# design.net
KiCad netlist of a schematic drawn in Altium Designer
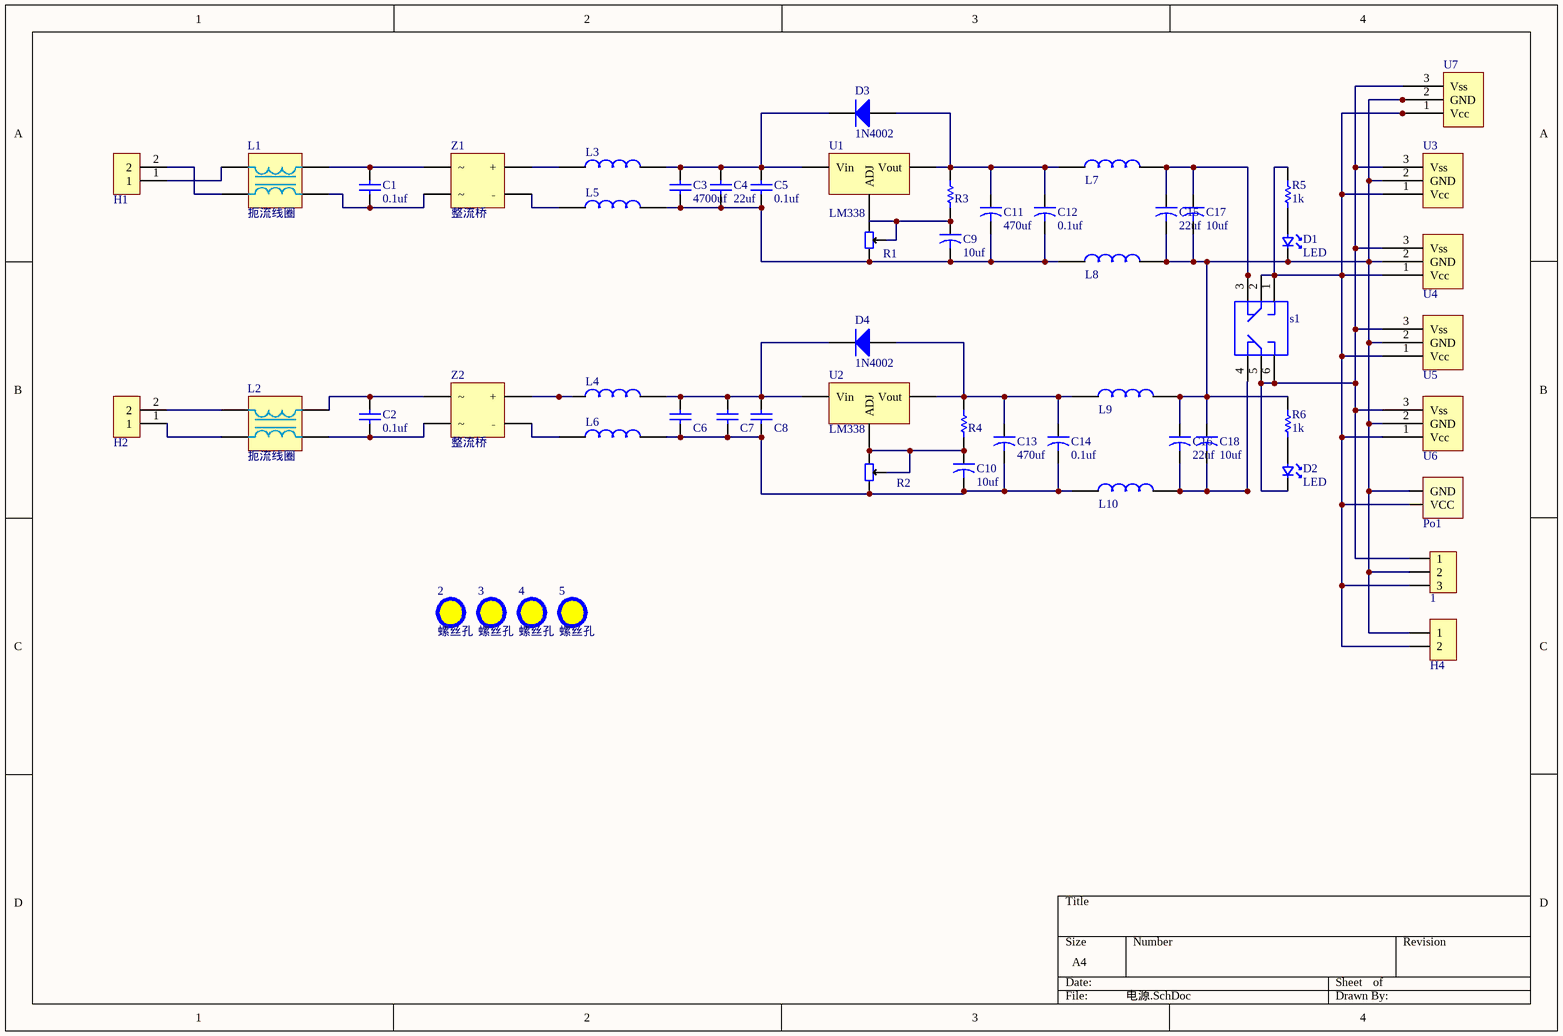
[diagram p0: 电源.SchDoc]

(export (version "E")
  (design (tool "Eeschema 10.0.6"))
  (components
    (comp (ref "1")
      (value "KF128-5.08-3P")
      (footprint "KF128-5.08-3P")
      (libsource (lib "Mylib_Connectors") (part "KF128-5.08-3P"))
    )
    (comp (ref "2") (value "螺丝孔") (footprint "固定过孔") (libsource (lib "Mylib_Connectors") (part "螺丝孔")))
    (comp (ref "3") (value "螺丝孔") (footprint "固定过孔") (libsource (lib "Mylib_Connectors") (part "螺丝孔")))
    (comp (ref "4") (value "螺丝孔") (footprint "固定过孔") (libsource (lib "Mylib_Connectors") (part "螺丝孔")))
    (comp (ref "5") (value "螺丝孔") (footprint "固定过孔") (libsource (lib "Mylib_Connectors") (part "螺丝孔")))
    (comp (ref "C1")
      (value "~")
      (footprint "安规电容")
      (fields (field (name "值") "0.1uf"))
      (libsource (lib "SCH_lib_tao") (part "Cap1"))
    )
    (comp (ref "C2")
      (value "Cap1")
      (footprint "安规电容")
      (fields (field (name "值") "0.1uf"))
      (libsource (lib "SCH_lib_tao") (part "Cap1"))
    )
    (comp (ref "C3")
      (value "Cap1")
      (footprint "4700UF_50V")
      (fields (field (name "值") "4700uf"))
      (libsource (lib "SCH_lib_tao") (part "Cap1"))
    )
    (comp (ref "C4")
      (value "Cap1")
      (footprint "22UF_50V")
      (fields (field (name "值") "22uf"))
      (libsource (lib "SCH_lib_tao") (part "Cap1"))
    )
    (comp (ref "C5")
      (value "Cap1")
      (footprint "独石电容")
      (fields (field (name "值") "0.1uf"))
      (libsource (lib "SCH_lib_tao") (part "Cap1"))
    )
    (comp (ref "C6") (value "Cap1") (footprint "4700UF_50V") (libsource (lib "SCH_lib_tao") (part "Cap1")))
    (comp (ref "C7") (value "Cap1") (footprint "22UF_50V") (libsource (lib "SCH_lib_tao") (part "Cap1")))
    (comp (ref "C8") (value "Cap1") (footprint "独石电容") (libsource (lib "SCH_lib_tao") (part "Cap1")))
    (comp (ref "C9")
      (value "Cap")
      (footprint "陶瓷电容")
      (fields (field (name "值") "10uf"))
      (libsource (lib "SCH_lib_tao") (part "Cap"))
    )
    (comp (ref "C10")
      (value "Cap")
      (footprint "陶瓷电容")
      (fields (field (name "值") "10uf"))
      (libsource (lib "SCH_lib_tao") (part "Cap"))
    )
    (comp (ref "C11")
      (value "Cap")
      (footprint "C DIP DIA6.3")
      (fields (field (name "值") "470uf"))
      (libsource (lib "SCH_lib_tao") (part "Cap"))
    )
    (comp (ref "C12")
      (value "Cap")
      (footprint "陶瓷电容")
      (fields (field (name "值") "0.1uf"))
      (libsource (lib "SCH_lib_tao") (part "Cap"))
    )
    (comp (ref "C13")
      (value "Cap")
      (footprint "C DIP DIA6.3")
      (fields (field (name "值") "470uf"))
      (libsource (lib "SCH_lib_tao") (part "Cap"))
    )
    (comp (ref "C14")
      (value "Cap")
      (footprint "陶瓷电容")
      (fields (field (name "值") "0.1uf"))
      (libsource (lib "SCH_lib_tao") (part "Cap"))
    )
    (comp (ref "C15")
      (value "Cap")
      (footprint "22UF_50V")
      (fields (field (name "值") "22uf"))
      (libsource (lib "SCH_lib_tao") (part "Cap"))
    )
    (comp (ref "C16")
      (value "Cap")
      (footprint "22UF_50V")
      (fields (field (name "值") "22uf"))
      (libsource (lib "SCH_lib_tao") (part "Cap"))
    )
    (comp (ref "C17")
      (value "Cap")
      (footprint "陶瓷电容")
      (fields (field (name "值") "10uf"))
      (libsource (lib "SCH_lib_tao") (part "Cap"))
    )
    (comp (ref "C18")
      (value "Cap")
      (footprint "陶瓷电容")
      (fields (field (name "值") "10uf"))
      (libsource (lib "SCH_lib_tao") (part "Cap"))
    )
    (comp (ref "D1") (value "LED") (footprint "0805_s") (libsource (lib "SCH_lib_tao") (part "LED")))
    (comp (ref "D2") (value "LED") (footprint "0805_s") (libsource (lib "SCH_lib_tao") (part "LED")))
    (comp (ref "D3")
      (value "1N4002")
      (footprint "SMC")
      (description "Default Diode")
      (fields (field (name "PUBLISHER") "Altium Limited"))
      (libsource (lib "Miscellaneous Devices") (part "Diode"))
    )
    (comp (ref "D4")
      (value "1N4002")
      (footprint "SMC")
      (description "Default Diode")
      (fields (field (name "PUBLISHER") "Altium Limited"))
      (libsource (lib "Miscellaneous Devices") (part "Diode"))
    )
    (comp (ref "H1")
      (value "HT3.96-2P")
      (footprint "HT39.6-2P-S")
      (libsource (lib "Mylib_Connectors") (part "HT3.96-2P"))
    )
    (comp (ref "H2")
      (value "HT3.96-2P")
      (footprint "HT39.6-2P-S")
      (libsource (lib "Mylib_Connectors") (part "HT3.96-2P"))
    )
    (comp (ref "H4")
      (value "KF128-5.08-2P")
      (footprint "KF128-5.08-2P")
      (libsource (lib "Mylib_Connectors") (part "KF128-5.08-2P"))
    )
    (comp (ref "L1") (value "扼流线圈") (footprint "扼流线圈") (libsource (lib "SCH_lib_tao") (part "扼流线圈")))
    (comp (ref "L2") (value "扼流线圈") (footprint "扼流线圈") (libsource (lib "SCH_lib_tao") (part "扼流线圈")))
    (comp (ref "L3")
      (value "SMD")
      (footprint "功率电感-12x12 - duplicate")
      (libsource (lib "Mylib_Common") (part "功率电感"))
    )
    (comp (ref "L4")
      (value "SMD")
      (footprint "功率电感-12x12 - duplicate")
      (libsource (lib "Mylib_Common") (part "功率电感"))
    )
    (comp (ref "L5")
      (value "SMD")
      (footprint "功率电感-12x12 - duplicate")
      (libsource (lib "Mylib_Common") (part "功率电感"))
    )
    (comp (ref "L6")
      (value "SMD")
      (footprint "功率电感-12x12 - duplicate")
      (libsource (lib "Mylib_Common") (part "功率电感"))
    )
    (comp (ref "L7")
      (value "SMD")
      (footprint "功率电感-12x12 - duplicate")
      (libsource (lib "Mylib_Common") (part "功率电感"))
    )
    (comp (ref "L8")
      (value "SMD")
      (footprint "功率电感-12x12 - duplicate")
      (libsource (lib "Mylib_Common") (part "功率电感"))
    )
    (comp (ref "L9")
      (value "SMD")
      (footprint "功率电感-12x12 - duplicate")
      (libsource (lib "Mylib_Common") (part "功率电感"))
    )
    (comp (ref "L10")
      (value "SMD")
      (footprint "功率电感-12x12 - duplicate")
      (libsource (lib "Mylib_Common") (part "功率电感"))
    )
    (comp (ref "Po1")
      (value "Power_2Port")
      (footprint "Power_S_2Port")
      (libsource (lib "Mylib_Connectors") (part "Power_2Port"))
    )
    (comp (ref "R1") (value "可调电位器1") (footprint "电位器") (libsource (lib "SCH_lib_tao") (part "可调电位器1")))
    (comp (ref "R2") (value "可调电位器1") (footprint "电位器") (libsource (lib "SCH_lib_tao") (part "可调电位器1")))
    (comp (ref "R3") (value "RES") (footprint "0805") (libsource (lib "SCH_lib_tao") (part "RES")))
    (comp (ref "R4") (value "RES") (footprint "0805") (libsource (lib "SCH_lib_tao") (part "RES")))
    (comp (ref "R5")
      (value "RES")
      (footprint "0805")
      (fields (field (name "值") "1k"))
      (libsource (lib "SCH_lib_tao") (part "RES"))
    )
    (comp (ref "R6")
      (value "RES")
      (footprint "0805")
      (fields (field (name "值") "1k"))
      (libsource (lib "SCH_lib_tao") (part "RES"))
    )
    (comp (ref "s1") (value "双掷开关") (footprint "SWITCH") (libsource (lib "SCH_lib_tao") (part "双掷开关")))
    (comp (ref "U1") (value "LM338") (footprint "LM338") (libsource (lib "SCH_lib_tao") (part "LM338")))
    (comp (ref "U2") (value "LM338") (footprint "LM338") (libsource (lib "SCH_lib_tao") (part "LM338")))
    (comp (ref "U3")
      (value "XH2.54-3p")
      (footprint "XH2.54-3p")
      (libsource (lib "SCH_lib_tao") (part "XH2.54-3p"))
    )
    (comp (ref "U4")
      (value "XH2.54-3p")
      (footprint "XH2.54-3p")
      (libsource (lib "SCH_lib_tao") (part "XH2.54-3p"))
    )
    (comp (ref "U5")
      (value "XH2.54-3p")
      (footprint "XH2.54-3p")
      (libsource (lib "SCH_lib_tao") (part "XH2.54-3p"))
    )
    (comp (ref "U6")
      (value "XH2.54-3p")
      (footprint "XH2.54-3p")
      (libsource (lib "SCH_lib_tao") (part "XH2.54-3p"))
    )
    (comp (ref "U7")
      (value "XH2.54-3p")
      (footprint "XH2.54-3p")
      (libsource (lib "SCH_lib_tao") (part "XH2.54-3p"))
    )
    (comp (ref "Z1") (value "整流桥") (footprint "整流桥") (libsource (lib "SCH_lib_tao") (part "整流桥")))
    (comp (ref "Z2") (value "整流桥") (footprint "整流桥") (libsource (lib "SCH_lib_tao") (part "整流桥")))
  )
  (nets
    (net (code "1") (name "Net-(C1-Pad1)") (class "Default")
      (node (ref "C1") (pin "1") (pinfunction "1_1") (pintype "passive"))
      (node (ref "L1") (pin "3") (pinfunction "3_3") (pintype "passive"))
      (node (ref "Z1") (pin "3") (pinfunction "~_3") (pintype "passive"))
    )
    (net (code "2") (name "Net-(C1-Pad2)") (class "Default")
      (node (ref "C1") (pin "2") (pinfunction "2_2") (pintype "passive"))
      (node (ref "L1") (pin "2") (pinfunction "2_2") (pintype "passive"))
      (node (ref "Z1") (pin "2") (pinfunction "~_2") (pintype "passive"))
    )
    (net (code "3") (name "Net-(C2-Pad1)") (class "Default")
      (node (ref "C2") (pin "1") (pinfunction "1_1") (pintype "passive"))
      (node (ref "L2") (pin "3") (pinfunction "3_3") (pintype "passive"))
      (node (ref "Z2") (pin "3") (pinfunction "~_3") (pintype "passive"))
    )
    (net (code "4") (name "Net-(C2-Pad2)") (class "Default")
      (node (ref "C2") (pin "2") (pinfunction "2_2") (pintype "passive"))
      (node (ref "L2") (pin "2") (pinfunction "2_2") (pintype "passive"))
      (node (ref "Z2") (pin "2") (pinfunction "~_2") (pintype "passive"))
    )
    (net (code "5") (name "Net-(C10-Pad2)") (class "Default")
      (node (ref "C10") (pin "2") (pinfunction "2_2") (pintype "passive"))
      (node (ref "C13") (pin "2") (pinfunction "2_2") (pintype "passive"))
      (node (ref "C14") (pin "2") (pinfunction "2_2") (pintype "passive"))
      (node (ref "C6") (pin "2") (pinfunction "2_2") (pintype "passive"))
      (node (ref "C7") (pin "2") (pinfunction "2_2") (pintype "passive"))
      (node (ref "C8") (pin "2") (pinfunction "2_2") (pintype "passive"))
      (node (ref "L10") (pin "1") (pintype "passive"))
      (node (ref "L6") (pin "2") (pintype "passive"))
      (node (ref "R2") (pin "1") (pinfunction "1_1") (pintype "passive"))
    )
    (net (code "6") (name "Net-(C11-Pad2)") (class "Default")
      (node (ref "C11") (pin "2") (pinfunction "2_2") (pintype "passive"))
      (node (ref "C12") (pin "2") (pinfunction "2_2") (pintype "passive"))
      (node (ref "C3") (pin "2") (pinfunction "2_2") (pintype "passive"))
      (node (ref "C4") (pin "2") (pinfunction "2_2") (pintype "passive"))
      (node (ref "C5") (pin "2") (pinfunction "2_2") (pintype "passive"))
      (node (ref "C9") (pin "2") (pinfunction "2_2") (pintype "passive"))
      (node (ref "L5") (pin "2") (pintype "passive"))
      (node (ref "L8") (pin "1") (pintype "passive"))
      (node (ref "R1") (pin "1") (pinfunction "1_1") (pintype "passive"))
    )
    (net (code "7") (name "Net-(C15-Pad1)") (class "Default")
      (node (ref "C15") (pin "1") (pinfunction "1_1") (pintype "passive"))
      (node (ref "C17") (pin "1") (pinfunction "1_1") (pintype "passive"))
      (node (ref "L7") (pin "2") (pintype "passive"))
      (node (ref "s1") (pin "3") (pinfunction "3_3") (pintype "passive"))
    )
    (net (code "8") (name "Net-(C16-Pad2)") (class "Default")
      (node (ref "C16") (pin "2") (pinfunction "2_2") (pintype "passive"))
      (node (ref "C18") (pin "2") (pinfunction "2_2") (pintype "passive"))
      (node (ref "L10") (pin "2") (pintype "passive"))
      (node (ref "s1") (pin "4") (pinfunction "4_4") (pintype "passive"))
    )
    (net (code "9") (name "Net-(D1-Pad2)") (class "Default")
      (node (ref "D1") (pin "2") (pinfunction "2_2") (pintype "passive"))
      (node (ref "R5") (pin "1") (pinfunction "1_1") (pintype "passive"))
    )
    (net (code "10") (name "Net-(D2-Pad2)") (class "Default")
      (node (ref "D2") (pin "2") (pinfunction "2_2") (pintype "passive"))
      (node (ref "R6") (pin "1") (pinfunction "1_1") (pintype "passive"))
    )
    (net (code "11") (name "Net-(D3-A)") (class "Default")
      (node (ref "C11") (pin "1") (pinfunction "1_1") (pintype "passive"))
      (node (ref "C12") (pin "1") (pinfunction "1_1") (pintype "passive"))
      (node (ref "D3") (pin "1") (pinfunction "A_1") (pintype "passive"))
      (node (ref "L7") (pin "1") (pintype "passive"))
      (node (ref "R3") (pin "2") (pinfunction "2_2") (pintype "passive"))
      (node (ref "U1") (pin "3") (pinfunction "Vout_3") (pintype "passive"))
    )
    (net (code "12") (name "Net-(D3-K)") (class "Default")
      (node (ref "C3") (pin "1") (pinfunction "1_1") (pintype "passive"))
      (node (ref "C4") (pin "1") (pinfunction "1_1") (pintype "passive"))
      (node (ref "C5") (pin "1") (pinfunction "1_1") (pintype "passive"))
      (node (ref "D3") (pin "2") (pinfunction "K_2") (pintype "passive"))
      (node (ref "L3") (pin "2") (pintype "passive"))
      (node (ref "U1") (pin "1") (pinfunction "Vin_1") (pintype "passive"))
    )
    (net (code "13") (name "Net-(D4-A)") (class "Default")
      (node (ref "C13") (pin "1") (pinfunction "1_1") (pintype "passive"))
      (node (ref "C14") (pin "1") (pinfunction "1_1") (pintype "passive"))
      (node (ref "D4") (pin "1") (pinfunction "A_1") (pintype "passive"))
      (node (ref "L9") (pin "1") (pintype "passive"))
      (node (ref "R4") (pin "2") (pinfunction "2_2") (pintype "passive"))
      (node (ref "U2") (pin "3") (pinfunction "Vout_3") (pintype "passive"))
    )
    (net (code "14") (name "Net-(D4-K)") (class "Default")
      (node (ref "C6") (pin "1") (pinfunction "1_1") (pintype "passive"))
      (node (ref "C7") (pin "1") (pinfunction "1_1") (pintype "passive"))
      (node (ref "C8") (pin "1") (pinfunction "1_1") (pintype "passive"))
      (node (ref "D4") (pin "2") (pinfunction "K_2") (pintype "passive"))
      (node (ref "L4") (pin "2") (pintype "passive"))
      (node (ref "U2") (pin "1") (pinfunction "Vin_1") (pintype "passive"))
    )
    (net (code "15") (name "Net-(H1-Pad1)") (class "Default")
      (node (ref "H1") (pin "1") (pinfunction "1_1") (pintype "passive"))
      (node (ref "L1") (pin "1") (pinfunction "1_1") (pintype "passive"))
    )
    (net (code "16") (name "Net-(H1-Pad2)") (class "Default")
      (node (ref "H1") (pin "2") (pinfunction "2_2") (pintype "passive"))
      (node (ref "L1") (pin "4") (pinfunction "4_4") (pintype "passive"))
    )
    (net (code "17") (name "Net-(H2-Pad1)") (class "Default")
      (node (ref "H2") (pin "1") (pinfunction "1_1") (pintype "passive"))
      (node (ref "L2") (pin "4") (pinfunction "4_4") (pintype "passive"))
    )
    (net (code "18") (name "Net-(H2-Pad2)") (class "Default")
      (node (ref "H2") (pin "2") (pinfunction "2_2") (pintype "passive"))
      (node (ref "L2") (pin "1") (pinfunction "1_1") (pintype "passive"))
    )
    (net (code "19") (name "Net-(Po1-GND)") (class "Default")
      (node (ref "1") (pin "2") (pinfunction "2_2") (pintype "passive"))
      (node (ref "C15") (pin "2") (pinfunction "2_2") (pintype "passive"))
      (node (ref "C16") (pin "1") (pinfunction "1_1") (pintype "passive"))
      (node (ref "C17") (pin "2") (pinfunction "2_2") (pintype "passive"))
      (node (ref "C18") (pin "1") (pinfunction "1_1") (pintype "passive"))
      (node (ref "D1") (pin "1") (pinfunction "1_1") (pintype "passive"))
      (node (ref "H4") (pin "1") (pinfunction "1_1") (pintype "passive"))
      (node (ref "L8") (pin "2") (pintype "passive"))
      (node (ref "L9") (pin "2") (pintype "passive"))
      (node (ref "Po1") (pin "2") (pinfunction "GND_2") (pintype "passive"))
      (node (ref "R6") (pin "2") (pinfunction "2_2") (pintype "passive"))
      (node (ref "U3") (pin "2") (pinfunction "GND_2") (pintype "passive"))
      (node (ref "U4") (pin "2") (pinfunction "GND_2") (pintype "passive"))
      (node (ref "U5") (pin "2") (pinfunction "GND_2") (pintype "passive"))
      (node (ref "U6") (pin "2") (pinfunction "GND_2") (pintype "passive"))
      (node (ref "U7") (pin "2") (pinfunction "GND_2") (pintype "passive"))
    )
    (net (code "20") (name "Net-(Po1-VCC)") (class "Default")
      (node (ref "1") (pin "3") (pinfunction "3_3") (pintype "passive"))
      (node (ref "H4") (pin "2") (pinfunction "2_2") (pintype "passive"))
      (node (ref "Po1") (pin "1") (pinfunction "VCC_1") (pintype "passive"))
      (node (ref "R5") (pin "2") (pinfunction "2_2") (pintype "passive"))
      (node (ref "U3") (pin "1") (pinfunction "Vcc_1") (pintype "passive"))
      (node (ref "U4") (pin "1") (pinfunction "Vcc_1") (pintype "passive"))
      (node (ref "U5") (pin "1") (pinfunction "Vcc_1") (pintype "passive"))
      (node (ref "U6") (pin "1") (pinfunction "Vcc_1") (pintype "passive"))
      (node (ref "U7") (pin "1") (pinfunction "Vcc_1") (pintype "passive"))
      (node (ref "s1") (pin "1") (pinfunction "1_1") (pintype "passive"))
      (node (ref "s1") (pin "2") (pinfunction "2_2") (pintype "passive"))
    )
    (net (code "21") (name "Net-(U1-ADJ)") (class "Default")
      (node (ref "C9") (pin "1") (pinfunction "1_1") (pintype "passive"))
      (node (ref "R1") (pin "2") (pinfunction "2_2") (pintype "passive"))
      (node (ref "R3") (pin "1") (pinfunction "1_1") (pintype "passive"))
      (node (ref "U1") (pin "2") (pinfunction "ADJ_2") (pintype "passive"))
    )
    (net (code "22") (name "Net-(U2-ADJ)") (class "Default")
      (node (ref "C10") (pin "1") (pinfunction "1_1") (pintype "passive"))
      (node (ref "R2") (pin "2") (pinfunction "2_2") (pintype "passive"))
      (node (ref "R2") (pin "3") (pinfunction "3_3") (pintype "passive"))
      (node (ref "R4") (pin "1") (pinfunction "1_1") (pintype "passive"))
      (node (ref "U2") (pin "2") (pinfunction "ADJ_2") (pintype "passive"))
    )
    (net (code "23") (name "Net-(U3-Vss)") (class "Default")
      (node (ref "1") (pin "1") (pinfunction "1_1") (pintype "passive"))
      (node (ref "D2") (pin "1") (pinfunction "1_1") (pintype "passive"))
      (node (ref "U3") (pin "3") (pinfunction "Vss_3") (pintype "passive"))
      (node (ref "U4") (pin "3") (pinfunction "Vss_3") (pintype "passive"))
      (node (ref "U5") (pin "3") (pinfunction "Vss_3") (pintype "passive"))
      (node (ref "U6") (pin "3") (pinfunction "Vss_3") (pintype "passive"))
      (node (ref "U7") (pin "3") (pinfunction "Vss_3") (pintype "passive"))
      (node (ref "s1") (pin "5") (pinfunction "5_5") (pintype "passive"))
      (node (ref "s1") (pin "6") (pinfunction "6_6") (pintype "passive"))
    )
    (net (code "24") (name "Net-(Z1-+)") (class "Default")
      (node (ref "L3") (pin "1") (pintype "passive"))
      (node (ref "Z1") (pin "1") (pinfunction "+_1") (pintype "passive"))
    )
    (net (code "25") (name "Net-(Z1-﹣)") (class "Default")
      (node (ref "L5") (pin "1") (pintype "passive"))
      (node (ref "Z1") (pin "4") (pinfunction "﹣_4") (pintype "passive"))
    )
    (net (code "26") (name "Net-(Z2-+)") (class "Default")
      (node (ref "L4") (pin "1") (pintype "passive"))
      (node (ref "Z2") (pin "1") (pinfunction "+_1") (pintype "passive"))
    )
    (net (code "27") (name "Net-(Z2-﹣)") (class "Default")
      (node (ref "L6") (pin "1") (pintype "passive"))
      (node (ref "Z2") (pin "4") (pinfunction "﹣_4") (pintype "passive"))
    )
    (net (code "28") (name "unconnected-(R1-Pad3)") (class "Default")
      (node (ref "R1") (pin "3") (pinfunction "3_3") (pintype "passive"))
    )
  )
)
